# Fingerprint_lock_1_2.net
KiCad netlist of a schematic drawn in EAGLE
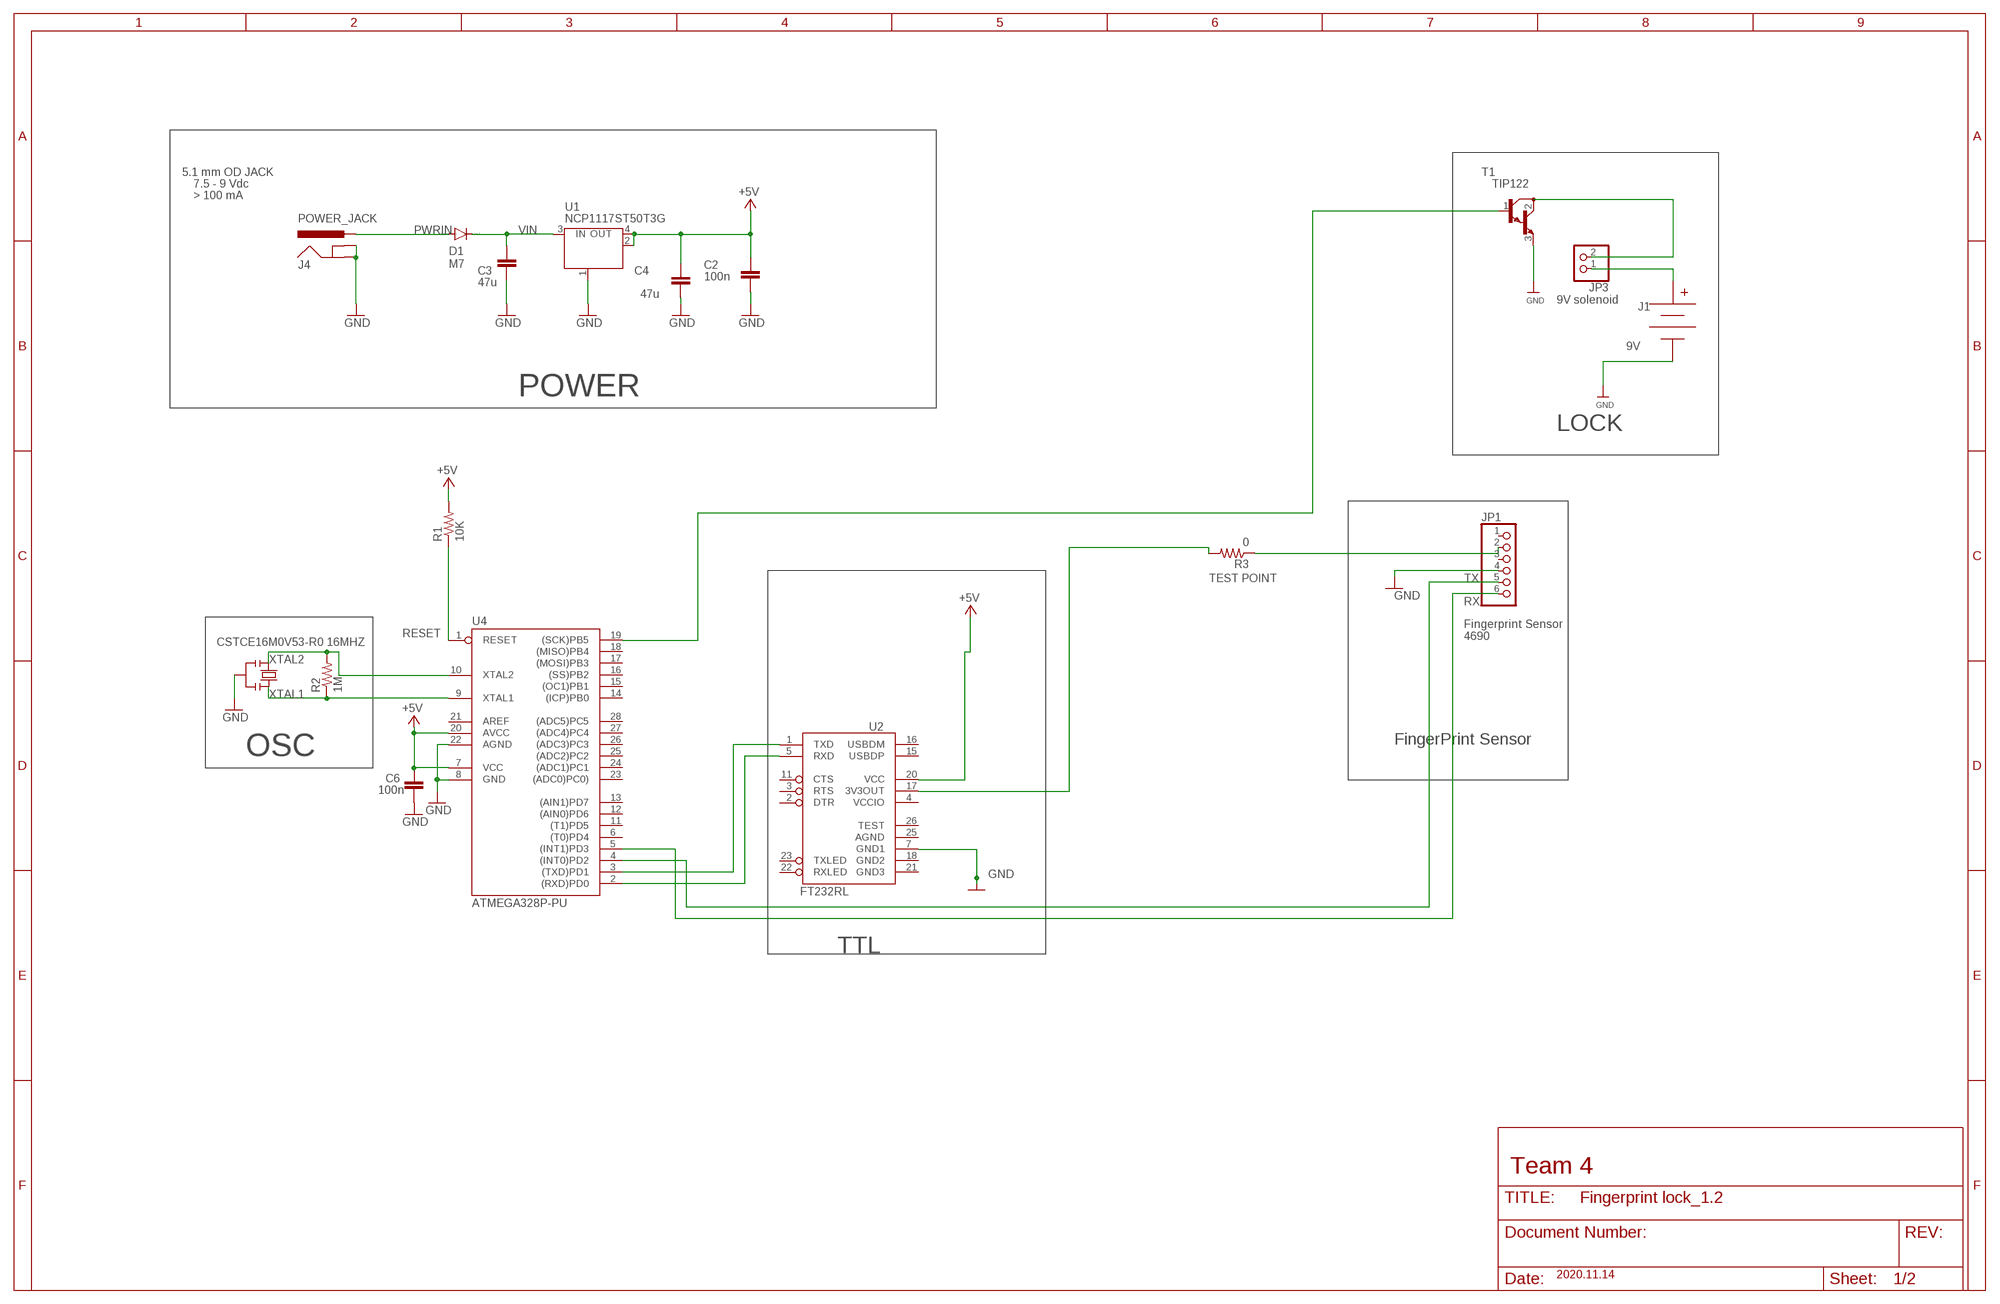
[diagram p0: schematic, sheet 1]

(export (version "E")
  (design (tool "Eeschema 10.0.6"))
  (components
    (comp (ref "C2")
      (value "100n")
      (footprint "eagle-import:C0805")
      (libsource (lib "eagle-import") (part "C-EUC0805"))
    )
    (comp (ref "C3")
      (value "47u")
      (footprint "eagle-import:C0805")
      (libsource (lib "eagle-import") (part "C-EUC0805"))
    )
    (comp (ref "C4")
      (value "47u")
      (footprint "eagle-import:C0805")
      (libsource (lib "eagle-import") (part "C-EUC0805"))
    )
    (comp (ref "C6")
      (value "100n")
      (footprint "eagle-import:C0805")
      (libsource (lib "eagle-import") (part "C-EUC0805"))
    )
    (comp (ref "D1")
      (value "M7")
      (footprint "eagle-import:SMB")
      (libsource (lib "eagle-import") (part "DIODE-SMB"))
    )
    (comp (ref "J1")
      (value "9V")
      (footprint "eagle-import:BC9VPC")
      (libsource (lib "eagle-import") (part "BC9VPC"))
    )
    (comp (ref "J4")
      (value "POWER_JACK")
      (footprint "eagle-import:POWER_JACK_PTH")
      (libsource (lib "eagle-import") (part "POWER_JACK"))
    )
    (comp (ref "JP1")
      (value "PINHD-1X6B")
      (footprint "eagle-import:1X06-BIG")
      (libsource (lib "eagle-import") (part "PINHD-1X6B"))
    )
    (comp (ref "JP3")
      (value "PINHD-1X2")
      (footprint "eagle-import:1X02")
      (libsource (lib "eagle-import") (part "PINHD-1X2"))
    )
    (comp (ref "R1")
      (value "10K")
      (footprint "eagle-import:R0805")
      (libsource (lib "eagle-import") (part "R-US_R0805"))
    )
    (comp (ref "R2")
      (value "1M")
      (footprint "eagle-import:R0805")
      (libsource (lib "eagle-import") (part "R-US_R0805"))
    )
    (comp (ref "R3")
      (value "0")
      (footprint "eagle-import:R0805")
      (libsource (lib "eagle-import") (part "R-US_R0805"))
    )
    (comp (ref "T1")
      (value "TIP122")
      (footprint "eagle-import:TO220")
      (libsource (lib "eagle-import") (part "TIP122"))
    )
    (comp (ref "U1")
      (value "NCP1117ST50T3G")
      (footprint "eagle-import:SOT223")
      (libsource (lib "eagle-import") (part "MC33269ST-3.3T3"))
    )
    (comp (ref "U2")
      (value "FT232RL")
      (footprint "eagle-import:SSOP28DB")
      (libsource (lib "eagle-import") (part "FT232RL-BASICSSOP"))
    )
    (comp (ref "U4")
      (value "ATMEGA328P-PU")
      (footprint "eagle-import:DIL28-3")
      (libsource (lib "eagle-import") (part "ATMEGA328P-PU"))
    )
    (comp (ref "X1")
      (value "CSTCE16M0V53-R0 16MHZ")
      (footprint "eagle-import:RESONATOR")
      (libsource (lib "eagle-import") (part "RESONATORMU"))
    )
  )
  (nets
    (net (code "1") (name "+5V") (class "Default")
      (node (ref "C2") (pin "2") (pinfunction "2_2") (pintype "passive"))
      (node (ref "C4") (pin "2") (pinfunction "2_2") (pintype "passive"))
      (node (ref "C6") (pin "2") (pinfunction "2_2") (pintype "passive"))
      (node (ref "R1") (pin "2") (pinfunction "2_2") (pintype "passive"))
      (node (ref "U1") (pin "2") (pinfunction "OUT_2") (pintype "passive"))
      (node (ref "U1") (pin "4") (pinfunction "OUT_4") (pintype "passive"))
      (node (ref "U2") (pin "20") (pinfunction "VCC_20") (pintype "power_in"))
      (node (ref "U4") (pin "20") (pinfunction "AVCC_20") (pintype "power_in"))
      (node (ref "U4") (pin "7") (pinfunction "VCC_7") (pintype "power_in"))
    )
    (net (code "2") (name "AGND") (class "Default")
      (node (ref "U2") (pin "25") (pinfunction "AGND_25") (pintype "power_in"))
    )
    (net (code "3") (name "GND") (class "Default")
      (node (ref "C2") (pin "1") (pinfunction "1_1") (pintype "passive"))
      (node (ref "C3") (pin "1") (pinfunction "1_1") (pintype "passive"))
      (node (ref "C4") (pin "1") (pinfunction "1_1") (pintype "passive"))
      (node (ref "C6") (pin "1") (pinfunction "1_1") (pintype "passive"))
      (node (ref "J1") (pin "V-") (pinfunction "V-_V-") (pintype "bidirectional"))
      (node (ref "J4") (pin "GND") (pinfunction "GND_GND") (pintype "bidirectional"))
      (node (ref "J4") (pin "GNDBREAK") (pinfunction "GNDBREAK_GNDBREAK") (pintype "bidirectional"))
      (node (ref "JP1") (pin "4") (pinfunction "4_4") (pintype "passive"))
      (node (ref "T1") (pin "3") (pinfunction "E_3") (pintype "passive"))
      (node (ref "U1") (pin "1") (pinfunction "GND/ADJ_1") (pintype "input"))
      (node (ref "U2") (pin "7") (pinfunction "GND1_7") (pintype "power_in"))
      (node (ref "U4") (pin "22") (pinfunction "AGND_22") (pintype "power_in"))
      (node (ref "U4") (pin "8") (pinfunction "GND_8") (pintype "power_in"))
      (node (ref "X1") (pin "2") (pinfunction "2_2") (pintype "passive"))
    )
    (net (code "4") (name "GND2") (class "Default")
      (node (ref "U2") (pin "18") (pinfunction "GND2_18") (pintype "power_in"))
    )
    (net (code "5") (name "GND3") (class "Default")
      (node (ref "U2") (pin "21") (pinfunction "GND3_21") (pintype "power_in"))
    )
    (net (code "6") (name "Net-(J1-PadV+)") (class "Default")
      (node (ref "J1") (pin "V+") (pinfunction "V+_V+") (pintype "bidirectional"))
      (node (ref "JP3") (pin "1") (pinfunction "1_1") (pintype "passive"))
    )
    (net (code "7") (name "Net-(JP1-Pad2)") (class "Default")
      (node (ref "JP1") (pin "2") (pinfunction "2_2") (pintype "passive"))
      (node (ref "R3") (pin "1") (pinfunction "1_1") (pintype "passive"))
    )
    (net (code "8") (name "Net-(T1-B)") (class "Default")
      (node (ref "T1") (pin "1") (pinfunction "B_1") (pintype "passive"))
      (node (ref "U4") (pin "19") (pinfunction "(SCK)PB5_19") (pintype "bidirectional"))
    )
    (net (code "9") (name "Net-(T1-C)") (class "Default")
      (node (ref "JP3") (pin "2") (pinfunction "2_2") (pintype "passive"))
      (node (ref "T1") (pin "2") (pinfunction "C_2") (pintype "passive"))
    )
    (net (code "10") (name "Net-(U2-3V3OUT)") (class "Default")
      (node (ref "R3") (pin "2") (pinfunction "2_2") (pintype "passive"))
      (node (ref "U2") (pin "17") (pinfunction "3V3OUT_17") (pintype "output"))
    )
    (net (code "11") (name "Net-(U2-RXD)") (class "Default")
      (node (ref "U2") (pin "5") (pinfunction "RXD_5") (pintype "input"))
      (node (ref "U4") (pin "2") (pinfunction "(RXD)PD0_2") (pintype "bidirectional"))
    )
    (net (code "12") (name "Net-(U2-TXD)") (class "Default")
      (node (ref "U2") (pin "1") (pinfunction "TXD_1") (pintype "output"))
      (node (ref "U4") (pin "3") (pinfunction "(TXD)PD1_3") (pintype "bidirectional"))
    )
    (net (code "13") (name "Net-(U4-(INT0)PD2)") (class "Default")
      (node (ref "JP1") (pin "5") (pinfunction "5_5") (pintype "passive"))
      (node (ref "U4") (pin "4") (pinfunction "(INT0)PD2_4") (pintype "bidirectional"))
    )
    (net (code "14") (name "Net-(U4-(INT1)PD3)") (class "Default")
      (node (ref "JP1") (pin "6") (pinfunction "6_6") (pintype "passive"))
      (node (ref "U4") (pin "5") (pinfunction "(INT1)PD3_5") (pintype "bidirectional"))
    )
    (net (code "15") (name "PWRIN") (class "Default")
      (node (ref "D1") (pin "A") (pinfunction "A_A") (pintype "passive"))
      (node (ref "J4") (pin "PWR") (pinfunction "PWR_PWR") (pintype "bidirectional"))
    )
    (net (code "16") (name "RESET") (class "Default")
      (node (ref "R1") (pin "1") (pinfunction "1_1") (pintype "passive"))
      (node (ref "U4") (pin "1") (pinfunction "RESET_1") (pintype "input"))
    )
    (net (code "17") (name "VCCIO") (class "Default")
      (node (ref "U2") (pin "4") (pinfunction "VCCIO_4") (pintype "power_in"))
    )
    (net (code "18") (name "VIN") (class "Default")
      (node (ref "C3") (pin "2") (pinfunction "2_2") (pintype "passive"))
      (node (ref "D1") (pin "C") (pinfunction "C_C") (pintype "passive"))
      (node (ref "U1") (pin "3") (pinfunction "IN_3") (pintype "input"))
    )
    (net (code "19") (name "XTAL1") (class "Default")
      (node (ref "R2") (pin "1") (pinfunction "1_1") (pintype "passive"))
      (node (ref "U4") (pin "9") (pinfunction "XTAL1_9") (pintype "bidirectional"))
      (node (ref "X1") (pin "3") (pinfunction "3_3") (pintype "passive"))
    )
    (net (code "20") (name "XTAL2") (class "Default")
      (node (ref "R2") (pin "2") (pinfunction "2_2") (pintype "passive"))
      (node (ref "U4") (pin "10") (pinfunction "XTAL2_10") (pintype "bidirectional"))
      (node (ref "X1") (pin "1") (pinfunction "1_1") (pintype "passive"))
    )
    (net (code "21") (name "unconnected-(JP1-Pad1)") (class "Default")
      (node (ref "JP1") (pin "1") (pinfunction "1_1") (pintype "passive"))
    )
    (net (code "22") (name "unconnected-(JP1-Pad3)") (class "Default")
      (node (ref "JP1") (pin "3") (pinfunction "3_3") (pintype "passive"))
    )
    (net (code "23") (name "unconnected-(U2-CTS-Pad11)") (class "Default")
      (node (ref "U2") (pin "11") (pinfunction "CTS_11") (pintype "bidirectional"))
    )
    (net (code "24") (name "unconnected-(U2-DTR-Pad2)") (class "Default")
      (node (ref "U2") (pin "2") (pinfunction "DTR_2") (pintype "bidirectional"))
    )
    (net (code "25") (name "unconnected-(U2-RTS-Pad3)") (class "Default")
      (node (ref "U2") (pin "3") (pinfunction "RTS_3") (pintype "bidirectional"))
    )
    (net (code "26") (name "unconnected-(U2-RXLED-Pad22)") (class "Default")
      (node (ref "U2") (pin "22") (pinfunction "RXLED_22") (pintype "bidirectional"))
    )
    (net (code "27") (name "unconnected-(U2-TEST-Pad26)") (class "Default")
      (node (ref "U2") (pin "26") (pinfunction "TEST_26") (pintype "input"))
    )
    (net (code "28") (name "unconnected-(U2-TXLED-Pad23)") (class "Default")
      (node (ref "U2") (pin "23") (pinfunction "TXLED_23") (pintype "bidirectional"))
    )
    (net (code "29") (name "unconnected-(U2-USBDM-Pad16)") (class "Default")
      (node (ref "U2") (pin "16") (pinfunction "USBDM_16") (pintype "bidirectional"))
    )
    (net (code "30") (name "unconnected-(U2-USBDP-Pad15)") (class "Default")
      (node (ref "U2") (pin "15") (pinfunction "USBDP_15") (pintype "bidirectional"))
    )
    (net (code "31") (name "unconnected-(U4-(ADC0)PC0)-Pad23)") (class "Default")
      (node (ref "U4") (pin "23") (pinfunction "(ADC0)PC0)_23") (pintype "bidirectional"))
    )
    (net (code "32") (name "unconnected-(U4-(ADC1)PC1-Pad24)") (class "Default")
      (node (ref "U4") (pin "24") (pinfunction "(ADC1)PC1_24") (pintype "bidirectional"))
    )
    (net (code "33") (name "unconnected-(U4-(ADC2)PC2-Pad25)") (class "Default")
      (node (ref "U4") (pin "25") (pinfunction "(ADC2)PC2_25") (pintype "bidirectional"))
    )
    (net (code "34") (name "unconnected-(U4-(ADC3)PC3-Pad26)") (class "Default")
      (node (ref "U4") (pin "26") (pinfunction "(ADC3)PC3_26") (pintype "bidirectional"))
    )
    (net (code "35") (name "unconnected-(U4-(ADC4)PC4-Pad27)") (class "Default")
      (node (ref "U4") (pin "27") (pinfunction "(ADC4)PC4_27") (pintype "bidirectional"))
    )
    (net (code "36") (name "unconnected-(U4-(ADC5)PC5-Pad28)") (class "Default")
      (node (ref "U4") (pin "28") (pinfunction "(ADC5)PC5_28") (pintype "bidirectional"))
    )
    (net (code "37") (name "unconnected-(U4-(AIN0)PD6-Pad12)") (class "Default")
      (node (ref "U4") (pin "12") (pinfunction "(AIN0)PD6_12") (pintype "bidirectional"))
    )
    (net (code "38") (name "unconnected-(U4-(AIN1)PD7-Pad13)") (class "Default")
      (node (ref "U4") (pin "13") (pinfunction "(AIN1)PD7_13") (pintype "bidirectional"))
    )
    (net (code "39") (name "unconnected-(U4-(ICP)PB0-Pad14)") (class "Default")
      (node (ref "U4") (pin "14") (pinfunction "(ICP)PB0_14") (pintype "bidirectional"))
    )
    (net (code "40") (name "unconnected-(U4-(MISO)PB4-Pad18)") (class "Default")
      (node (ref "U4") (pin "18") (pinfunction "(MISO)PB4_18") (pintype "bidirectional"))
    )
    (net (code "41") (name "unconnected-(U4-(MOSI)PB3-Pad17)") (class "Default")
      (node (ref "U4") (pin "17") (pinfunction "(MOSI)PB3_17") (pintype "bidirectional"))
    )
    (net (code "42") (name "unconnected-(U4-(OC1)PB1-Pad15)") (class "Default")
      (node (ref "U4") (pin "15") (pinfunction "(OC1)PB1_15") (pintype "bidirectional"))
    )
    (net (code "43") (name "unconnected-(U4-(SS)PB2-Pad16)") (class "Default")
      (node (ref "U4") (pin "16") (pinfunction "(SS)PB2_16") (pintype "bidirectional"))
    )
    (net (code "44") (name "unconnected-(U4-(T0)PD4-Pad6)") (class "Default")
      (node (ref "U4") (pin "6") (pinfunction "(T0)PD4_6") (pintype "bidirectional"))
    )
    (net (code "45") (name "unconnected-(U4-(T1)PD5-Pad11)") (class "Default")
      (node (ref "U4") (pin "11") (pinfunction "(T1)PD5_11") (pintype "bidirectional"))
    )
    (net (code "46") (name "unconnected-(U4-AREF-Pad21)") (class "Default")
      (node (ref "U4") (pin "21") (pinfunction "AREF_21") (pintype "passive"))
    )
  )
)
